# usb_connectors.net
KiCad netlist of a schematic drawn in Altium Designer
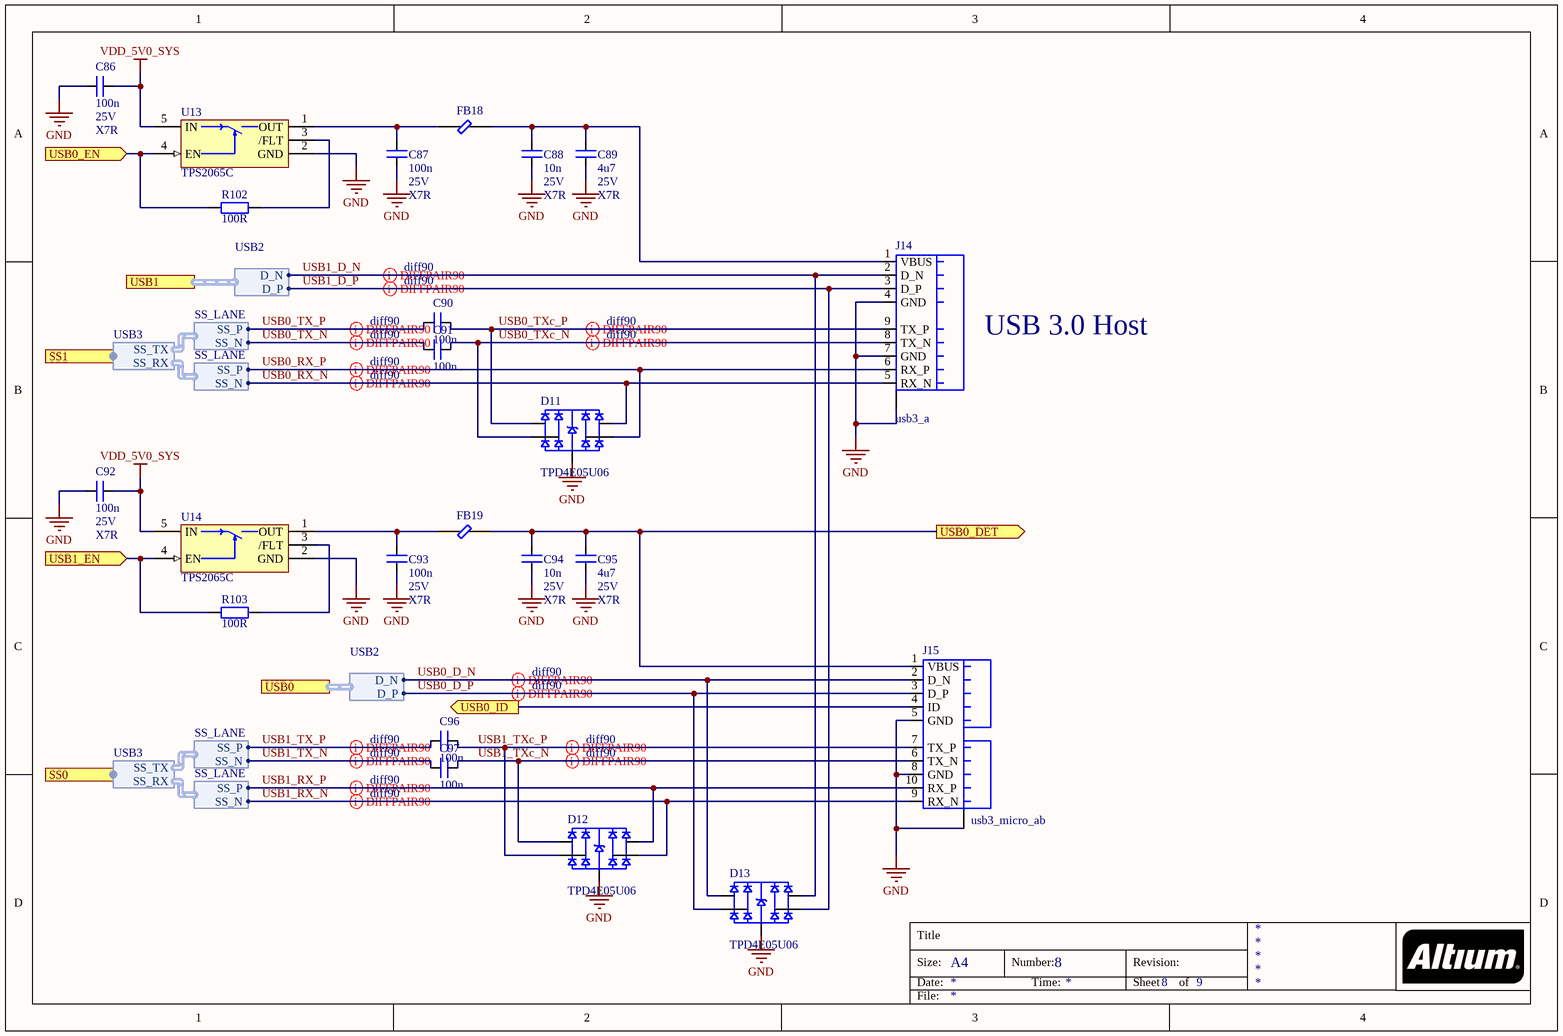
[diagram p0: usb_connectors.SchDoc]

(export (version "E")
  (design (tool "Eeschema 10.0.6"))
  (components
    (comp (ref "C86")
      (value "100n")
      (footprint "C1005[0402]")
      (description "Capacitor")
      (fields (field (name "VOLTAGE") "25V") (field (name "TYPE") "X7R") (field (name "Comment") "cap"))
      (libsource (lib "gpa_passives") (part "cap"))
    )
    (comp (ref "C87")
      (value "100n")
      (footprint "C1005[0402]")
      (description "Capacitor")
      (fields (field (name "VOLTAGE") "25V") (field (name "TYPE") "X7R") (field (name "Comment") "cap"))
      (libsource (lib "gpa_passives") (part "cap"))
    )
    (comp (ref "C88")
      (value "10n")
      (footprint "C1005[0402]")
      (description "Capacitor")
      (fields (field (name "VOLTAGE") "25V") (field (name "TYPE") "X7R") (field (name "Comment") "cap"))
      (libsource (lib "gpa_passives") (part "cap"))
    )
    (comp (ref "C89")
      (value "4u7")
      (footprint "C3216[1206]")
      (description "Capacitor")
      (fields (field (name "VOLTAGE") "25V") (field (name "TYPE") "X7R") (field (name "Comment") "cap"))
      (libsource (lib "gpa_passives") (part "cap"))
    )
    (comp (ref "C90")
      (value "100n")
      (footprint "C1005[0402]")
      (description "Capacitor")
      (fields (field (name "VOLTAGE") "25V") (field (name "Comment") "cap"))
      (libsource (lib "gpa_passives") (part "cap"))
    )
    (comp (ref "C91")
      (value "100n")
      (footprint "C1005[0402]")
      (description "Capacitor")
      (fields (field (name "VOLTAGE") "25V") (field (name "Comment") "cap"))
      (libsource (lib "gpa_passives") (part "cap"))
    )
    (comp (ref "C92")
      (value "100n")
      (footprint "C1005[0402]")
      (description "Capacitor")
      (fields (field (name "VOLTAGE") "25V") (field (name "TYPE") "X7R") (field (name "Comment") "cap"))
      (libsource (lib "gpa_passives") (part "cap"))
    )
    (comp (ref "C93")
      (value "100n")
      (footprint "C1005[0402]")
      (description "Capacitor")
      (fields (field (name "VOLTAGE") "25V") (field (name "TYPE") "X7R") (field (name "Comment") "cap"))
      (libsource (lib "gpa_passives") (part "cap"))
    )
    (comp (ref "C94")
      (value "10n")
      (footprint "C1005[0402]")
      (description "Capacitor")
      (fields (field (name "VOLTAGE") "25V") (field (name "TYPE") "X7R") (field (name "Comment") "cap"))
      (libsource (lib "gpa_passives") (part "cap"))
    )
    (comp (ref "C95")
      (value "4u7")
      (footprint "C3216[1206]")
      (description "Capacitor")
      (fields (field (name "VOLTAGE") "25V") (field (name "TYPE") "X7R") (field (name "Comment") "cap"))
      (libsource (lib "gpa_passives") (part "cap"))
    )
    (comp (ref "C96")
      (value "100n")
      (footprint "C1005[0402]")
      (description "Capacitor")
      (fields (field (name "VOLTAGE") "25V") (field (name "Comment") "cap"))
      (libsource (lib "gpa_passives") (part "cap"))
    )
    (comp (ref "C97")
      (value "100n")
      (footprint "C1005[0402]")
      (description "Capacitor")
      (fields (field (name "VOLTAGE") "25V") (field (name "Comment") "cap"))
      (libsource (lib "gpa_passives") (part "cap"))
    )
    (comp (ref "D11")
      (value "TPD4E05U06")
      (footprint "TI_PSON50P100X55-10N")
      (libsource (lib "gpa_ti") (part "tpd4e05u06"))
    )
    (comp (ref "D12")
      (value "TPD4E05U06")
      (footprint "TI_PSON50P100X55-10N")
      (libsource (lib "gpa_ti") (part "tpd4e05u06"))
    )
    (comp (ref "D13")
      (value "TPD4E05U06")
      (footprint "TI_PSON50P100X55-10N")
      (libsource (lib "gpa_ti") (part "tpd4e05u06"))
    )
    (comp (ref "FB18")
      (value "2506036007Y3")
      (footprint "FBC1608X07N")
      (description "Ferrite bead")
      (libsource (lib "gpa_passives") (part "ferrite_bead"))
    )
    (comp (ref "FB19")
      (value "2506036007Y3")
      (footprint "FBC1608X07N")
      (description "Ferrite bead")
      (libsource (lib "gpa_passives") (part "ferrite_bead"))
    )
    (comp (ref "J14")
      (value "usb3_a")
      (footprint "usb3_a")
      (libsource (lib "gpa_connectors") (part "usb3_a"))
    )
    (comp (ref "J15")
      (value "usb3_micro_ab")
      (footprint "usb3_micro_ab")
      (libsource (lib "gpa_connectors") (part "usb3_micro_ab"))
    )
    (comp (ref "R102")
      (value "100R")
      (footprint "R1005[0402]")
      (description "Resistor")
      (fields (field (name "Comment") "res"))
      (libsource (lib "gpa_passives") (part "res"))
    )
    (comp (ref "R103")
      (value "100R")
      (footprint "R1005[0402]")
      (description "Resistor")
      (fields (field (name "Comment") "res"))
      (libsource (lib "gpa_passives") (part "res"))
    )
    (comp (ref "U13")
      (value "TPS2065C")
      (footprint "TI_SOT95P280X145-5N")
      (libsource (lib "gpa_ti") (part "tps2065c"))
    )
    (comp (ref "U14")
      (value "TPS2065C")
      (footprint "TI_SOT95P280X145-5N")
      (libsource (lib "gpa_ti") (part "tps2065c"))
    )
  )
  (nets
    (net (code "7") (name "/USB0_DET") (class "Default")
      (node (ref "C94") (pin "2") (pinfunction "2_2") (pintype "passive"))
      (node (ref "C95") (pin "2") (pinfunction "2_2") (pintype "passive"))
      (node (ref "FB19") (pin "2") (pinfunction "2_2") (pintype "passive"))
      (node (ref "J15") (pin "1") (pinfunction "VBUS_1") (pintype "passive"))
    )
    (net (code "8") (name "/USB0_D_N") (class "Default")
      (node (ref "D13") (pin "1") (pinfunction "D1+_1") (pintype "passive"))
      (node (ref "J15") (pin "2") (pinfunction "D_N_2") (pintype "passive"))
    )
    (net (code "9") (name "/USB0_D_P") (class "Default")
      (node (ref "D13") (pin "2") (pinfunction "D1-_2") (pintype "passive"))
      (node (ref "J15") (pin "3") (pinfunction "D_P_3") (pintype "passive"))
    )
    (net (code "10") (name "/USB0_EN") (class "Default")
      (node (ref "R102") (pin "1") (pinfunction "1_1") (pintype "passive"))
      (node (ref "U13") (pin "4") (pinfunction "EN_4") (pintype "input"))
    )
    (net (code "11") (name "/USB0_ID") (class "Default")
      (node (ref "J15") (pin "4") (pinfunction "ID_4") (pintype "passive"))
    )
    (net (code "12") (name "/USB0_RX_N") (class "Default")
      (node (ref "D11") (pin "5") (pinfunction "D2+_5") (pintype "passive"))
      (node (ref "J14") (pin "5") (pinfunction "RX_N_5") (pintype "passive"))
    )
    (net (code "13") (name "/USB0_RX_P") (class "Default")
      (node (ref "D11") (pin "4") (pinfunction "D2-_4") (pintype "passive"))
      (node (ref "J14") (pin "6") (pinfunction "RX_P_6") (pintype "passive"))
    )
    (net (code "14") (name "/USB0_TX_N") (class "Default")
      (node (ref "C91") (pin "2") (pinfunction "2_2") (pintype "passive"))
    )
    (net (code "15") (name "/USB0_TX_P") (class "Default")
      (node (ref "C90") (pin "2") (pinfunction "2_2") (pintype "passive"))
    )
    (net (code "16") (name "/USB0_TXc_N") (class "Default")
      (node (ref "C91") (pin "1") (pinfunction "1_1") (pintype "passive"))
      (node (ref "D11") (pin "2") (pinfunction "D1-_2") (pintype "passive"))
      (node (ref "J14") (pin "8") (pinfunction "TX_N_8") (pintype "passive"))
    )
    (net (code "17") (name "/USB0_TXc_P") (class "Default")
      (node (ref "C90") (pin "1") (pinfunction "1_1") (pintype "passive"))
      (node (ref "D11") (pin "1") (pinfunction "D1+_1") (pintype "passive"))
      (node (ref "J14") (pin "9") (pinfunction "TX_P_9") (pintype "passive"))
    )
    (net (code "18") (name "/USB1_D_N") (class "Default")
      (node (ref "D13") (pin "5") (pinfunction "D2+_5") (pintype "passive"))
      (node (ref "J14") (pin "2") (pinfunction "D_N_2") (pintype "passive"))
    )
    (net (code "19") (name "/USB1_D_P") (class "Default")
      (node (ref "D13") (pin "4") (pinfunction "D2-_4") (pintype "passive"))
      (node (ref "J14") (pin "3") (pinfunction "D_P_3") (pintype "passive"))
    )
    (net (code "20") (name "/USB1_EN") (class "Default")
      (node (ref "R103") (pin "1") (pinfunction "1_1") (pintype "passive"))
      (node (ref "U14") (pin "4") (pinfunction "EN_4") (pintype "input"))
    )
    (net (code "21") (name "/USB1_RX_N") (class "Default")
      (node (ref "D12") (pin "4") (pinfunction "D2-_4") (pintype "passive"))
      (node (ref "J15") (pin "9") (pinfunction "RX_N_9") (pintype "passive"))
    )
    (net (code "22") (name "/USB1_RX_P") (class "Default")
      (node (ref "D12") (pin "5") (pinfunction "D2+_5") (pintype "passive"))
      (node (ref "J15") (pin "10") (pinfunction "RX_P_10") (pintype "passive"))
    )
    (net (code "23") (name "/USB1_TX_N") (class "Default")
      (node (ref "C97") (pin "2") (pinfunction "2_2") (pintype "passive"))
    )
    (net (code "24") (name "/USB1_TX_P") (class "Default")
      (node (ref "C96") (pin "2") (pinfunction "2_2") (pintype "passive"))
    )
    (net (code "25") (name "/USB1_TXc_N") (class "Default")
      (node (ref "C97") (pin "1") (pinfunction "1_1") (pintype "passive"))
      (node (ref "D12") (pin "1") (pinfunction "D1+_1") (pintype "passive"))
      (node (ref "J15") (pin "6") (pinfunction "TX_N_6") (pintype "passive"))
    )
    (net (code "26") (name "/USB1_TXc_P") (class "Default")
      (node (ref "C96") (pin "1") (pinfunction "1_1") (pintype "passive"))
      (node (ref "D12") (pin "2") (pinfunction "D1-_2") (pintype "passive"))
      (node (ref "J15") (pin "7") (pinfunction "TX_P_7") (pintype "passive"))
    )
    (net (code "29") (name "GND") (class "Default")
      (node (ref "C86") (pin "2") (pinfunction "2_2") (pintype "passive"))
      (node (ref "C87") (pin "1") (pinfunction "1_1") (pintype "passive"))
      (node (ref "C88") (pin "1") (pinfunction "1_1") (pintype "passive"))
      (node (ref "C89") (pin "1") (pinfunction "1_1") (pintype "passive"))
      (node (ref "C92") (pin "2") (pinfunction "2_2") (pintype "passive"))
      (node (ref "C93") (pin "1") (pinfunction "1_1") (pintype "passive"))
      (node (ref "C94") (pin "1") (pinfunction "1_1") (pintype "passive"))
      (node (ref "C95") (pin "1") (pinfunction "1_1") (pintype "passive"))
      (node (ref "D11") (pin "3") (pinfunction "GND_3") (pintype "passive"))
      (node (ref "D12") (pin "3") (pinfunction "GND_3") (pintype "passive"))
      (node (ref "D13") (pin "3") (pinfunction "GND_3") (pintype "passive"))
      (node (ref "J14") (pin "4") (pinfunction "GND_4") (pintype "passive"))
      (node (ref "J14") (pin "7") (pinfunction "GND_7") (pintype "passive"))
      (node (ref "J14") (pin "SHIELD") (pinfunction "SHIELD_SHIELD") (pintype "passive"))
      (node (ref "J15") (pin "5") (pinfunction "GND_5") (pintype "passive"))
      (node (ref "J15") (pin "8") (pinfunction "GND_8") (pintype "passive"))
      (node (ref "J15") (pin "SHIELD") (pinfunction "SHIELD_SHIELD") (pintype "passive"))
      (node (ref "U13") (pin "2") (pinfunction "GND_2") (pintype "power_in"))
      (node (ref "U14") (pin "2") (pinfunction "GND_2") (pintype "power_in"))
    )
    (net (code "30") (name "Net-(J14-VBUS)") (class "Default")
      (node (ref "C88") (pin "2") (pinfunction "2_2") (pintype "passive"))
      (node (ref "C89") (pin "2") (pinfunction "2_2") (pintype "passive"))
      (node (ref "FB18") (pin "2") (pinfunction "2_2") (pintype "passive"))
      (node (ref "J14") (pin "1") (pinfunction "VBUS_1") (pintype "passive"))
    )
    (net (code "31") (name "Net-(U13-OUT)") (class "Default")
      (node (ref "C87") (pin "2") (pinfunction "2_2") (pintype "passive"))
      (node (ref "FB18") (pin "1") (pinfunction "1_1") (pintype "passive"))
      (node (ref "U13") (pin "1") (pinfunction "OUT_1") (pintype "power_in"))
    )
    (net (code "32") (name "Net-(U13-{slash}FLT)") (class "Default")
      (node (ref "R102") (pin "2") (pinfunction "2_2") (pintype "passive"))
      (node (ref "U13") (pin "3") (pinfunction "/FLT_3") (pintype "open_collector"))
    )
    (net (code "33") (name "Net-(U14-OUT)") (class "Default")
      (node (ref "C93") (pin "2") (pinfunction "2_2") (pintype "passive"))
      (node (ref "FB19") (pin "1") (pinfunction "1_1") (pintype "passive"))
      (node (ref "U14") (pin "1") (pinfunction "OUT_1") (pintype "power_in"))
    )
    (net (code "34") (name "Net-(U14-{slash}FLT)") (class "Default")
      (node (ref "R103") (pin "2") (pinfunction "2_2") (pintype "passive"))
      (node (ref "U14") (pin "3") (pinfunction "/FLT_3") (pintype "open_collector"))
    )
    (net (code "35") (name "VDD_5V0_SYS") (class "Default")
      (node (ref "C86") (pin "1") (pinfunction "1_1") (pintype "passive"))
      (node (ref "C92") (pin "1") (pinfunction "1_1") (pintype "passive"))
      (node (ref "U13") (pin "5") (pinfunction "IN_5") (pintype "power_in"))
      (node (ref "U14") (pin "5") (pinfunction "IN_5") (pintype "power_in"))
    )
  )
)
